# pcb.net
KiCad netlist of a schematic drawn in EAGLE
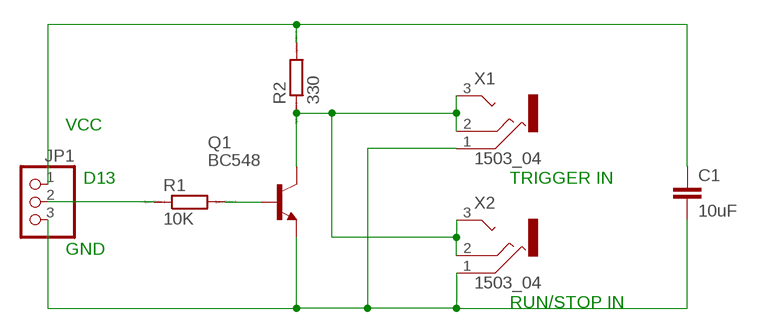
[diagram p0: schematic, sheet 1]

(export (version "E")
  (design (tool "Eeschema 10.0.6"))
  (components
    (comp (ref "C1")
      (value "10uF")
      (footprint "eagle-import:C050-035X075")
      (libsource (lib "eagle-import") (part "C-EU050-035X075"))
    )
    (comp (ref "JP1")
      (value "PINHD-1X3")
      (footprint "eagle-import:1X03")
      (libsource (lib "eagle-import") (part "PINHD-1X3"))
    )
    (comp (ref "Q1")
      (value "BC548")
      (footprint "eagle-import:TO92-EBC")
      (libsource (lib "eagle-import") (part "BC548"))
    )
    (comp (ref "R1")
      (value "10K")
      (footprint "eagle-import:0204_7")
      (libsource (lib "eagle-import") (part "R0204/7"))
    )
    (comp (ref "R2")
      (value "330")
      (footprint "eagle-import:0204_7")
      (libsource (lib "eagle-import") (part "R0204/7"))
    )
    (comp (ref "X1")
      (value "1503_04")
      (footprint "eagle-import:1503_04")
      (libsource (lib "eagle-import") (part "1503_04"))
    )
    (comp (ref "X2")
      (value "1503_04")
      (footprint "eagle-import:1503_04")
      (libsource (lib "eagle-import") (part "1503_04"))
    )
  )
  (nets
    (net (code "1") (name "Net-(C1-Pad1)") (class "Default")
      (node (ref "C1") (pin "1") (pinfunction "1_1") (pintype "passive"))
      (node (ref "JP1") (pin "1") (pinfunction "1_1") (pintype "passive"))
      (node (ref "R2") (pin "2") (pinfunction "2_2") (pintype "passive"))
    )
    (net (code "2") (name "Net-(C1-Pad2)") (class "Default")
      (node (ref "C1") (pin "2") (pinfunction "2_2") (pintype "passive"))
      (node (ref "JP1") (pin "3") (pinfunction "3_3") (pintype "passive"))
      (node (ref "Q1") (pin "E") (pinfunction "E_E") (pintype "passive"))
      (node (ref "X1") (pin "1") (pinfunction "1_1") (pintype "passive"))
      (node (ref "X2") (pin "1") (pinfunction "1_1") (pintype "passive"))
    )
    (net (code "3") (name "Net-(JP1-Pad2)") (class "Default")
      (node (ref "JP1") (pin "2") (pinfunction "2_2") (pintype "passive"))
      (node (ref "R1") (pin "1") (pinfunction "1_1") (pintype "passive"))
    )
    (net (code "4") (name "Net-(Q1-PadB)") (class "Default")
      (node (ref "Q1") (pin "B") (pinfunction "B_B") (pintype "passive"))
      (node (ref "R1") (pin "2") (pinfunction "2_2") (pintype "passive"))
    )
    (net (code "5") (name "Net-(X1-2)") (class "Default")
      (node (ref "Q1") (pin "C") (pinfunction "C_C") (pintype "passive"))
      (node (ref "R2") (pin "1") (pinfunction "1_1") (pintype "passive"))
      (node (ref "X1") (pin "2") (pinfunction "3_2") (pintype "passive"))
      (node (ref "X1") (pin "3") (pinfunction "2_3") (pintype "passive"))
      (node (ref "X2") (pin "2") (pinfunction "3_2") (pintype "passive"))
      (node (ref "X2") (pin "3") (pinfunction "2_3") (pintype "passive"))
    )
  )
)
